# Modulo_de_apertura_CPU.net
KiCad netlist of a schematic drawn in Altium Designer
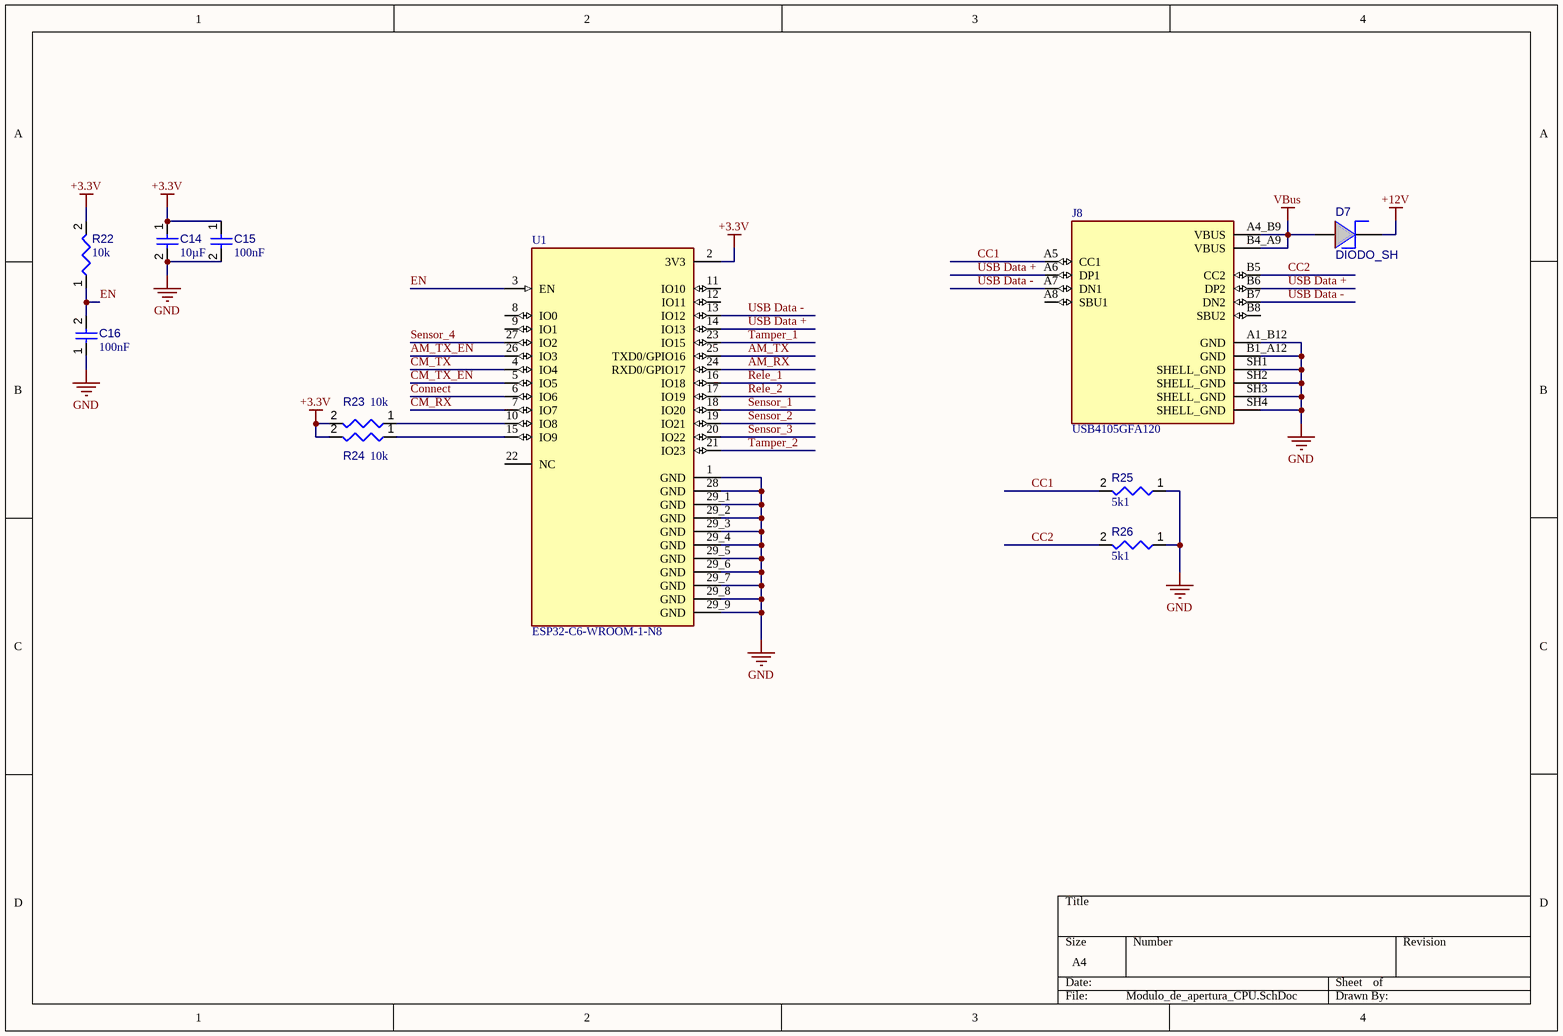
[diagram p0: Modulo_de_apertura_CPU.SchDoc]

(export (version "E")
  (design (tool "Eeschema 10.0.6"))
  (components
    (comp (ref "C14")
      (value "10µF")
      (footprint "CAPC0603(1608)100_L")
      (description "Chip Capacitor, 10µF +/-20%, 10V, 0603, Thickness 1 mm")
      (fields (field (name "TOLERANCE") "10%") (field (name "Comment") "Capacitor 10µF +/-20% 10V 0603"))
      (libsource (lib "Agustin Dubuisson") (part "CAP-NP-2"))
    )
    (comp (ref "C15")
      (value "100nF")
      (footprint "CAPC0402(1005)60_L")
      (description "Chip Capacitor, 100nF +/-20%, 10V, 0402, Thickness 0.6 mm")
      (fields (field (name "TOLERANCE") "20%") (field (name "Comment") "Capacitor 100nF +/-20% 10V 0402"))
      (libsource (lib "Agustin Dubuisson") (part "CAP-NP-2"))
    )
    (comp (ref "C16")
      (value "100nF")
      (footprint "CAPC0402(1005)33_L")
      (description "Chip Capacitor, 12pF +/-10%, 50V, 0402, Thickness 0.33 mm")
      (fields (field (name "TOLERANCE") "20%") (field (name "Comment") "Capacitor 12pF +/-10% 50V 0402"))
      (libsource (lib "Agustin Dubuisson") (part "CAP-NP-2"))
    )
    (comp (ref "D7")
      (value "DIODO_SH")
      (footprint "IDCI_WifiNode:D_SMA")
      (description "Diode Shottky")
      (libsource (lib "WifiNode") (part "DIODO_SH"))
    )
    (comp (ref "J8")
      (value "USB4105GFA120")
      (footprint "GCT_USB4105GFA120")
      (fields (field (name "MF") "Global Connector Technology"))
      (libsource (lib "USB4105GFA120") (part "USB4105GFA120"))
    )
    (comp (ref "R22")
      (value "10k")
      (footprint "RESC0402(1005)_L")
      (description "Chip Resistor, 10 kOhms, +/-1 %, 63 mW, -55 to 125 degC, 0402")
      (fields (field (name "POWER") "63mW") (field (name "TOLERANCE") "1%"))
      (libsource (lib "Agustin Dubuisson") (part "RES-2"))
    )
    (comp (ref "R23")
      (value "10k")
      (footprint "RESC0402(1005)_L")
      (description "Chip Resistor, 10 kOhms, +/-1 %, 63 mW, -55 to 125 degC, 0402")
      (fields (field (name "POWER") "63mW") (field (name "TOLERANCE") "1%"))
      (libsource (lib "Agustin Dubuisson") (part "RES-2"))
    )
    (comp (ref "R24")
      (value "10k")
      (footprint "RESC0402(1005)_L")
      (description "Chip Resistor, 10 kOhms, +/-1 %, 63 mW, -55 to 125 degC, 0402")
      (fields (field (name "POWER") "63mW") (field (name "TOLERANCE") "1%"))
      (libsource (lib "Agustin Dubuisson") (part "RES-2"))
    )
    (comp (ref "R25")
      (value "5k1")
      (footprint "RESC0402(1005)_L")
      (description "Chip Resistor, 10 kOhms, +/-1 %, 63 mW, -55 to 125 degC, 0402")
      (fields (field (name "POWER") "63mW") (field (name "TOLERANCE") "1%"))
      (libsource (lib "Agustin Dubuisson") (part "RES-2"))
    )
    (comp (ref "R26")
      (value "5k1")
      (footprint "RESC0402(1005)_L")
      (description "Chip Resistor, 10 kOhms, +/-1 %, 63 mW, -55 to 125 degC, 0402")
      (fields (field (name "POWER") "63mW") (field (name "TOLERANCE") "1%"))
      (libsource (lib "Agustin Dubuisson") (part "RES-2"))
    )
    (comp (ref "U1")
      (value "ESP32-C6-WROOM-1-N8")
      (footprint "XCVR_ESP32-C6-WROOM-1-N8")
      (fields (field (name "MF") "Espressif Systems"))
      (libsource (lib "ESP32-C6-WROOM-1-N8") (part "ESP32-C6-WROOM-1-N8"))
    )
  )
  (nets
    (net (code "1") (name "+3.3V") (class "Default")
      (node (ref "C14") (pin "1") (pinfunction "1_1") (pintype "passive"))
      (node (ref "C15") (pin "1") (pinfunction "1_1") (pintype "passive"))
      (node (ref "R22") (pin "2") (pinfunction "2_2") (pintype "passive"))
      (node (ref "R23") (pin "2") (pinfunction "2_2") (pintype "passive"))
      (node (ref "R24") (pin "2") (pinfunction "2_2") (pintype "passive"))
      (node (ref "U1") (pin "2") (pinfunction "3V3_2") (pintype "power_in"))
    )
    (net (code "2") (name "+12V") (class "Default")
      (node (ref "D7") (pin "2") (pinfunction "K_2") (pintype "passive"))
    )
    (net (code "3") (name "/AM_RX") (class "Default")
      (node (ref "U1") (pin "24") (pinfunction "RXD0/GPIO17_24") (pintype "bidirectional"))
    )
    (net (code "4") (name "/AM_TX") (class "Default")
      (node (ref "U1") (pin "25") (pinfunction "TXD0/GPIO16_25") (pintype "bidirectional"))
    )
    (net (code "5") (name "/AM_TX_EN") (class "Default")
      (node (ref "U1") (pin "26") (pinfunction "IO3_26") (pintype "bidirectional"))
    )
    (net (code "6") (name "/CC1") (class "Default")
      (node (ref "J8") (pin "A5") (pinfunction "CC1_A5") (pintype "bidirectional"))
      (node (ref "R25") (pin "2") (pinfunction "2_2") (pintype "passive"))
    )
    (net (code "7") (name "/CC2") (class "Default")
      (node (ref "J8") (pin "B5") (pinfunction "CC2_B5") (pintype "bidirectional"))
      (node (ref "R26") (pin "2") (pinfunction "2_2") (pintype "passive"))
    )
    (net (code "8") (name "/CM_RX") (class "Default")
      (node (ref "U1") (pin "7") (pinfunction "IO7_7") (pintype "bidirectional"))
    )
    (net (code "9") (name "/CM_TX") (class "Default")
      (node (ref "U1") (pin "4") (pinfunction "IO4_4") (pintype "bidirectional"))
    )
    (net (code "10") (name "/CM_TX_EN") (class "Default")
      (node (ref "U1") (pin "5") (pinfunction "IO5_5") (pintype "bidirectional"))
    )
    (net (code "11") (name "/Connect") (class "Default")
      (node (ref "U1") (pin "6") (pinfunction "IO6_6") (pintype "bidirectional"))
    )
    (net (code "12") (name "/EN") (class "Default")
      (node (ref "C16") (pin "2") (pinfunction "2_2") (pintype "passive"))
      (node (ref "R22") (pin "1") (pinfunction "1_1") (pintype "passive"))
      (node (ref "U1") (pin "3") (pinfunction "EN_3") (pintype "input"))
    )
    (net (code "13") (name "/Rele_1") (class "Default")
      (node (ref "U1") (pin "16") (pinfunction "IO18_16") (pintype "bidirectional"))
    )
    (net (code "14") (name "/Rele_2") (class "Default")
      (node (ref "U1") (pin "17") (pinfunction "IO19_17") (pintype "bidirectional"))
    )
    (net (code "15") (name "/Sensor_1") (class "Default")
      (node (ref "U1") (pin "18") (pinfunction "IO20_18") (pintype "bidirectional"))
    )
    (net (code "16") (name "/Sensor_2") (class "Default")
      (node (ref "U1") (pin "19") (pinfunction "IO21_19") (pintype "bidirectional"))
    )
    (net (code "17") (name "/Sensor_3") (class "Default")
      (node (ref "U1") (pin "20") (pinfunction "IO22_20") (pintype "bidirectional"))
    )
    (net (code "18") (name "/Sensor_4") (class "Default")
      (node (ref "U1") (pin "27") (pinfunction "IO2_27") (pintype "bidirectional"))
    )
    (net (code "19") (name "/Tamper_1") (class "Default")
      (node (ref "U1") (pin "23") (pinfunction "IO15_23") (pintype "bidirectional"))
    )
    (net (code "20") (name "/Tamper_2") (class "Default")
      (node (ref "U1") (pin "21") (pinfunction "IO23_21") (pintype "bidirectional"))
    )
    (net (code "21") (name "/USB Data +") (class "Default")
      (node (ref "J8") (pin "A6") (pinfunction "DP1_A6") (pintype "bidirectional"))
      (node (ref "J8") (pin "B6") (pinfunction "DP2_B6") (pintype "bidirectional"))
      (node (ref "U1") (pin "14") (pinfunction "IO13_14") (pintype "bidirectional"))
    )
    (net (code "22") (name "/USB Data -") (class "Default")
      (node (ref "J8") (pin "A7") (pinfunction "DN1_A7") (pintype "bidirectional"))
      (node (ref "J8") (pin "B7") (pinfunction "DN2_B7") (pintype "bidirectional"))
      (node (ref "U1") (pin "13") (pinfunction "IO12_13") (pintype "bidirectional"))
    )
    (net (code "23") (name "GND") (class "Default")
      (node (ref "C14") (pin "2") (pinfunction "2_2") (pintype "passive"))
      (node (ref "C15") (pin "2") (pinfunction "2_2") (pintype "passive"))
      (node (ref "C16") (pin "1") (pinfunction "1_1") (pintype "passive"))
      (node (ref "J8") (pin "A1_B12") (pinfunction "GND_A1_B12") (pintype "power_in"))
      (node (ref "J8") (pin "B1_A12") (pinfunction "GND_B1_A12") (pintype "power_in"))
      (node (ref "J8") (pin "SH1") (pinfunction "SHELL_GND_SH1") (pintype "power_in"))
      (node (ref "J8") (pin "SH2") (pinfunction "SHELL_GND_SH2") (pintype "power_in"))
      (node (ref "J8") (pin "SH3") (pinfunction "SHELL_GND_SH3") (pintype "power_in"))
      (node (ref "J8") (pin "SH4") (pinfunction "SHELL_GND_SH4") (pintype "power_in"))
      (node (ref "R25") (pin "1") (pinfunction "1_1") (pintype "passive"))
      (node (ref "R26") (pin "1") (pinfunction "1_1") (pintype "passive"))
      (node (ref "U1") (pin "1") (pinfunction "GND_1") (pintype "power_in"))
      (node (ref "U1") (pin "28") (pinfunction "GND_28") (pintype "power_in"))
      (node (ref "U1") (pin "29_1") (pinfunction "GND_29_1") (pintype "power_in"))
      (node (ref "U1") (pin "29_2") (pinfunction "GND_29_2") (pintype "power_in"))
      (node (ref "U1") (pin "29_3") (pinfunction "GND_29_3") (pintype "power_in"))
      (node (ref "U1") (pin "29_4") (pinfunction "GND_29_4") (pintype "power_in"))
      (node (ref "U1") (pin "29_5") (pinfunction "GND_29_5") (pintype "power_in"))
      (node (ref "U1") (pin "29_6") (pinfunction "GND_29_6") (pintype "power_in"))
      (node (ref "U1") (pin "29_7") (pinfunction "GND_29_7") (pintype "power_in"))
      (node (ref "U1") (pin "29_8") (pinfunction "GND_29_8") (pintype "power_in"))
      (node (ref "U1") (pin "29_9") (pinfunction "GND_29_9") (pintype "power_in"))
    )
    (net (code "24") (name "Net-(U1-IO8)") (class "Default")
      (node (ref "R23") (pin "1") (pinfunction "1_1") (pintype "passive"))
      (node (ref "U1") (pin "10") (pinfunction "IO8_10") (pintype "bidirectional"))
    )
    (net (code "25") (name "Net-(U1-IO9)") (class "Default")
      (node (ref "R24") (pin "1") (pinfunction "1_1") (pintype "passive"))
      (node (ref "U1") (pin "15") (pinfunction "IO9_15") (pintype "bidirectional"))
    )
    (net (code "26") (name "VBus") (class "Default")
      (node (ref "D7") (pin "1") (pinfunction "A_1") (pintype "passive"))
      (node (ref "J8") (pin "A4_B9") (pinfunction "VBUS_A4_B9") (pintype "power_in"))
      (node (ref "J8") (pin "B4_A9") (pinfunction "VBUS_B4_A9") (pintype "power_in"))
    )
    (net (code "27") (name "unconnected-(J8-SBU1-PadA8)") (class "Default")
      (node (ref "J8") (pin "A8") (pinfunction "SBU1_A8") (pintype "bidirectional"))
    )
    (net (code "28") (name "unconnected-(J8-SBU2-PadB8)") (class "Default")
      (node (ref "J8") (pin "B8") (pinfunction "SBU2_B8") (pintype "bidirectional"))
    )
    (net (code "29") (name "unconnected-(U1-IO0-Pad8)") (class "Default")
      (node (ref "U1") (pin "8") (pinfunction "IO0_8") (pintype "bidirectional"))
    )
    (net (code "30") (name "unconnected-(U1-IO1-Pad9)") (class "Default")
      (node (ref "U1") (pin "9") (pinfunction "IO1_9") (pintype "bidirectional"))
    )
    (net (code "31") (name "unconnected-(U1-IO10-Pad11)") (class "Default")
      (node (ref "U1") (pin "11") (pinfunction "IO10_11") (pintype "bidirectional"))
    )
    (net (code "32") (name "unconnected-(U1-IO11-Pad12)") (class "Default")
      (node (ref "U1") (pin "12") (pinfunction "IO11_12") (pintype "bidirectional"))
    )
    (net (code "33") (name "unconnected-(U1-NC-Pad22)") (class "Default")
      (node (ref "U1") (pin "22") (pinfunction "NC_22") (pintype "passive"))
    )
  )
)
